# RS485.net
KiCad netlist of a schematic drawn in Altium Designer
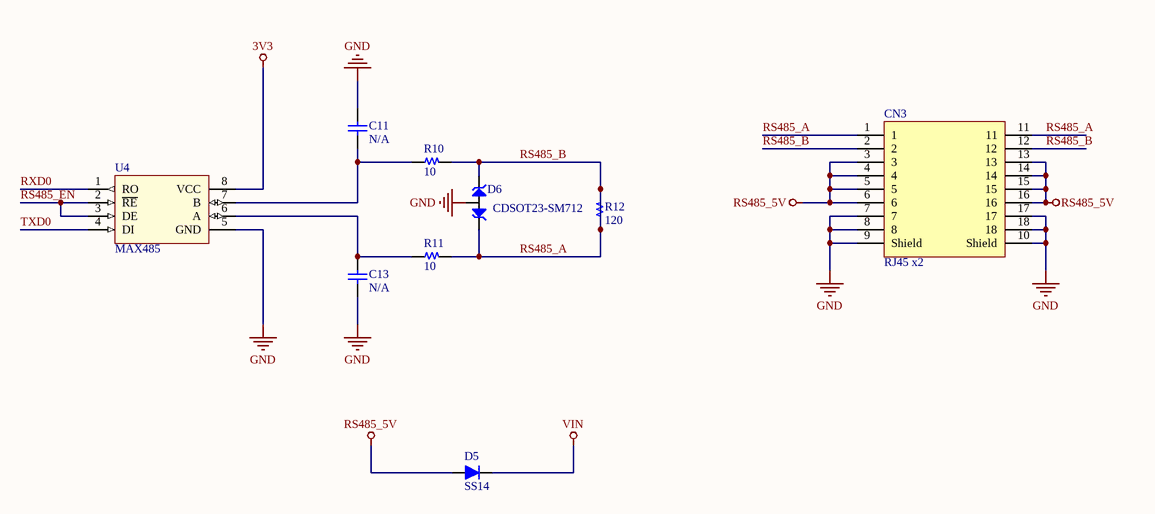
[diagram p0: RS485.SchDoc]

(export (version "E")
  (design (tool "Eeschema 10.0.6"))
  (components
    (comp (ref "C11")
      (value "N/A")
      (footprint "C 0805")
      (description "Capacitor non-pol")
      (libsource (lib "chipfc_libs") (part "Capacitor NP"))
    )
    (comp (ref "C13")
      (value "N/A")
      (footprint "C 0805")
      (description "Capacitor non-pol")
      (libsource (lib "chipfc_libs") (part "Capacitor NP"))
    )
    (comp (ref "CN3")
      (value "RJ45 x2")
      (footprint "CONN/RJ45/x2")
      (description "Connector RJ45 X2")
      (libsource (lib "connectors") (part "CON RJ45 x2"))
    )
    (comp (ref "D5")
      (value "SS14")
      (footprint "DO-35 (SOD27 )")
      (description "Default Diode")
      (libsource (lib "chipfc_libs") (part "Diode"))
    )
    (comp (ref "D6")
      (value "CDSOT23-SM712")
      (footprint "SOT-23")
      (description "TVS DIODE 7V/12V 14V/26V SOT23-3")
      (libsource (lib "chipfc_libs") (part "CDSOT23-SM712"))
    )
    (comp (ref "R10")
      (value "10")
      (footprint "R 0805")
      (description "Resistor")
      (libsource (lib "chipfc_libs") (part "Resistor"))
    )
    (comp (ref "R11")
      (value "10")
      (footprint "R 0805")
      (description "Resistor")
      (libsource (lib "chipfc_libs") (part "Resistor"))
    )
    (comp (ref "R12")
      (value "120")
      (footprint "R 0805")
      (description "Resistor")
      (libsource (lib "chipfc_libs") (part "Resistor"))
    )
    (comp (ref "U4")
      (value "MAX485")
      (footprint "SOIC-8")
      (description "Low-Power, Slew-Rate-Limited  RS-485/RS-422 Transceivers")
      (libsource (lib "bs_libs") (part "MAX485"))
    )
  )
  (nets
    (net (code "1") (name "/RS485_A") (class "Default")
      (node (ref "CN3") (pin "1") (pinfunction "1_1") (pintype "passive"))
      (node (ref "CN3") (pin "11") (pinfunction "11_11") (pintype "passive"))
      (node (ref "CN3") (pin "12") (pinfunction "12_12") (pintype "passive"))
      (node (ref "CN3") (pin "2") (pinfunction "2_2") (pintype "passive"))
      (node (ref "D6") (pin "1") (pinfunction "IO1_1") (pintype "passive"))
      (node (ref "D6") (pin "2") (pinfunction "IO2_2") (pintype "passive"))
      (node (ref "R10") (pin "2") (pinfunction "2_2") (pintype "passive"))
      (node (ref "R11") (pin "2") (pinfunction "2_2") (pintype "passive"))
      (node (ref "R12") (pin "1") (pinfunction "1_1") (pintype "passive"))
      (node (ref "R12") (pin "2") (pinfunction "2_2") (pintype "passive"))
    )
    (net (code "2") (name "/RS485_EN") (class "Default")
      (node (ref "U4") (pin "2") (pinfunction "~{RE}_2") (pintype "input"))
      (node (ref "U4") (pin "3") (pinfunction "DE_3") (pintype "input"))
    )
    (net (code "3") (name "/RXD0") (class "Default")
      (node (ref "U4") (pin "1") (pinfunction "RO_1") (pintype "output"))
    )
    (net (code "4") (name "/TXD0") (class "Default")
      (node (ref "U4") (pin "4") (pinfunction "DI_4") (pintype "input"))
    )
    (net (code "5") (name "3V3") (class "Default")
      (node (ref "U4") (pin "8") (pinfunction "VCC_8") (pintype "passive"))
    )
    (net (code "6") (name "GND") (class "Default")
      (node (ref "C11") (pin "1") (pinfunction "1_1") (pintype "passive"))
      (node (ref "C13") (pin "2") (pinfunction "2_2") (pintype "passive"))
      (node (ref "CN3") (pin "10") (pinfunction "Shield_10") (pintype "passive"))
      (node (ref "CN3") (pin "17") (pinfunction "17_17") (pintype "passive"))
      (node (ref "CN3") (pin "18") (pinfunction "18_18") (pintype "passive"))
      (node (ref "CN3") (pin "7") (pinfunction "7_7") (pintype "passive"))
      (node (ref "CN3") (pin "8") (pinfunction "8_8") (pintype "passive"))
      (node (ref "CN3") (pin "9") (pinfunction "Shield_9") (pintype "passive"))
      (node (ref "D6") (pin "3") (pinfunction "COM_3") (pintype "passive"))
      (node (ref "U4") (pin "5") (pinfunction "GND_5") (pintype "passive"))
    )
    (net (code "7") (name "Net-(U4-A)") (class "Default")
      (node (ref "C13") (pin "1") (pinfunction "1_1") (pintype "passive"))
      (node (ref "R11") (pin "1") (pinfunction "1_1") (pintype "passive"))
      (node (ref "U4") (pin "6") (pinfunction "A_6") (pintype "bidirectional"))
    )
    (net (code "8") (name "Net-(U4-B)") (class "Default")
      (node (ref "C11") (pin "2") (pinfunction "2_2") (pintype "passive"))
      (node (ref "R10") (pin "1") (pinfunction "1_1") (pintype "passive"))
      (node (ref "U4") (pin "7") (pinfunction "B_7") (pintype "bidirectional"))
    )
    (net (code "9") (name "RS485_5V") (class "Default")
      (node (ref "CN3") (pin "13") (pinfunction "13_13") (pintype "passive"))
      (node (ref "CN3") (pin "14") (pinfunction "14_14") (pintype "passive"))
      (node (ref "CN3") (pin "15") (pinfunction "15_15") (pintype "passive"))
      (node (ref "CN3") (pin "16") (pinfunction "16_16") (pintype "passive"))
      (node (ref "CN3") (pin "3") (pinfunction "3_3") (pintype "passive"))
      (node (ref "CN3") (pin "4") (pinfunction "4_4") (pintype "passive"))
      (node (ref "CN3") (pin "5") (pinfunction "5_5") (pintype "passive"))
      (node (ref "CN3") (pin "6") (pinfunction "6_6") (pintype "passive"))
      (node (ref "D5") (pin "1") (pinfunction "A_1") (pintype "passive"))
    )
    (net (code "10") (name "VIN") (class "Default")
      (node (ref "D5") (pin "2") (pinfunction "K_2") (pintype "passive"))
    )
  )
)
